# design.net
KiCad netlist of a schematic drawn in Altium Designer
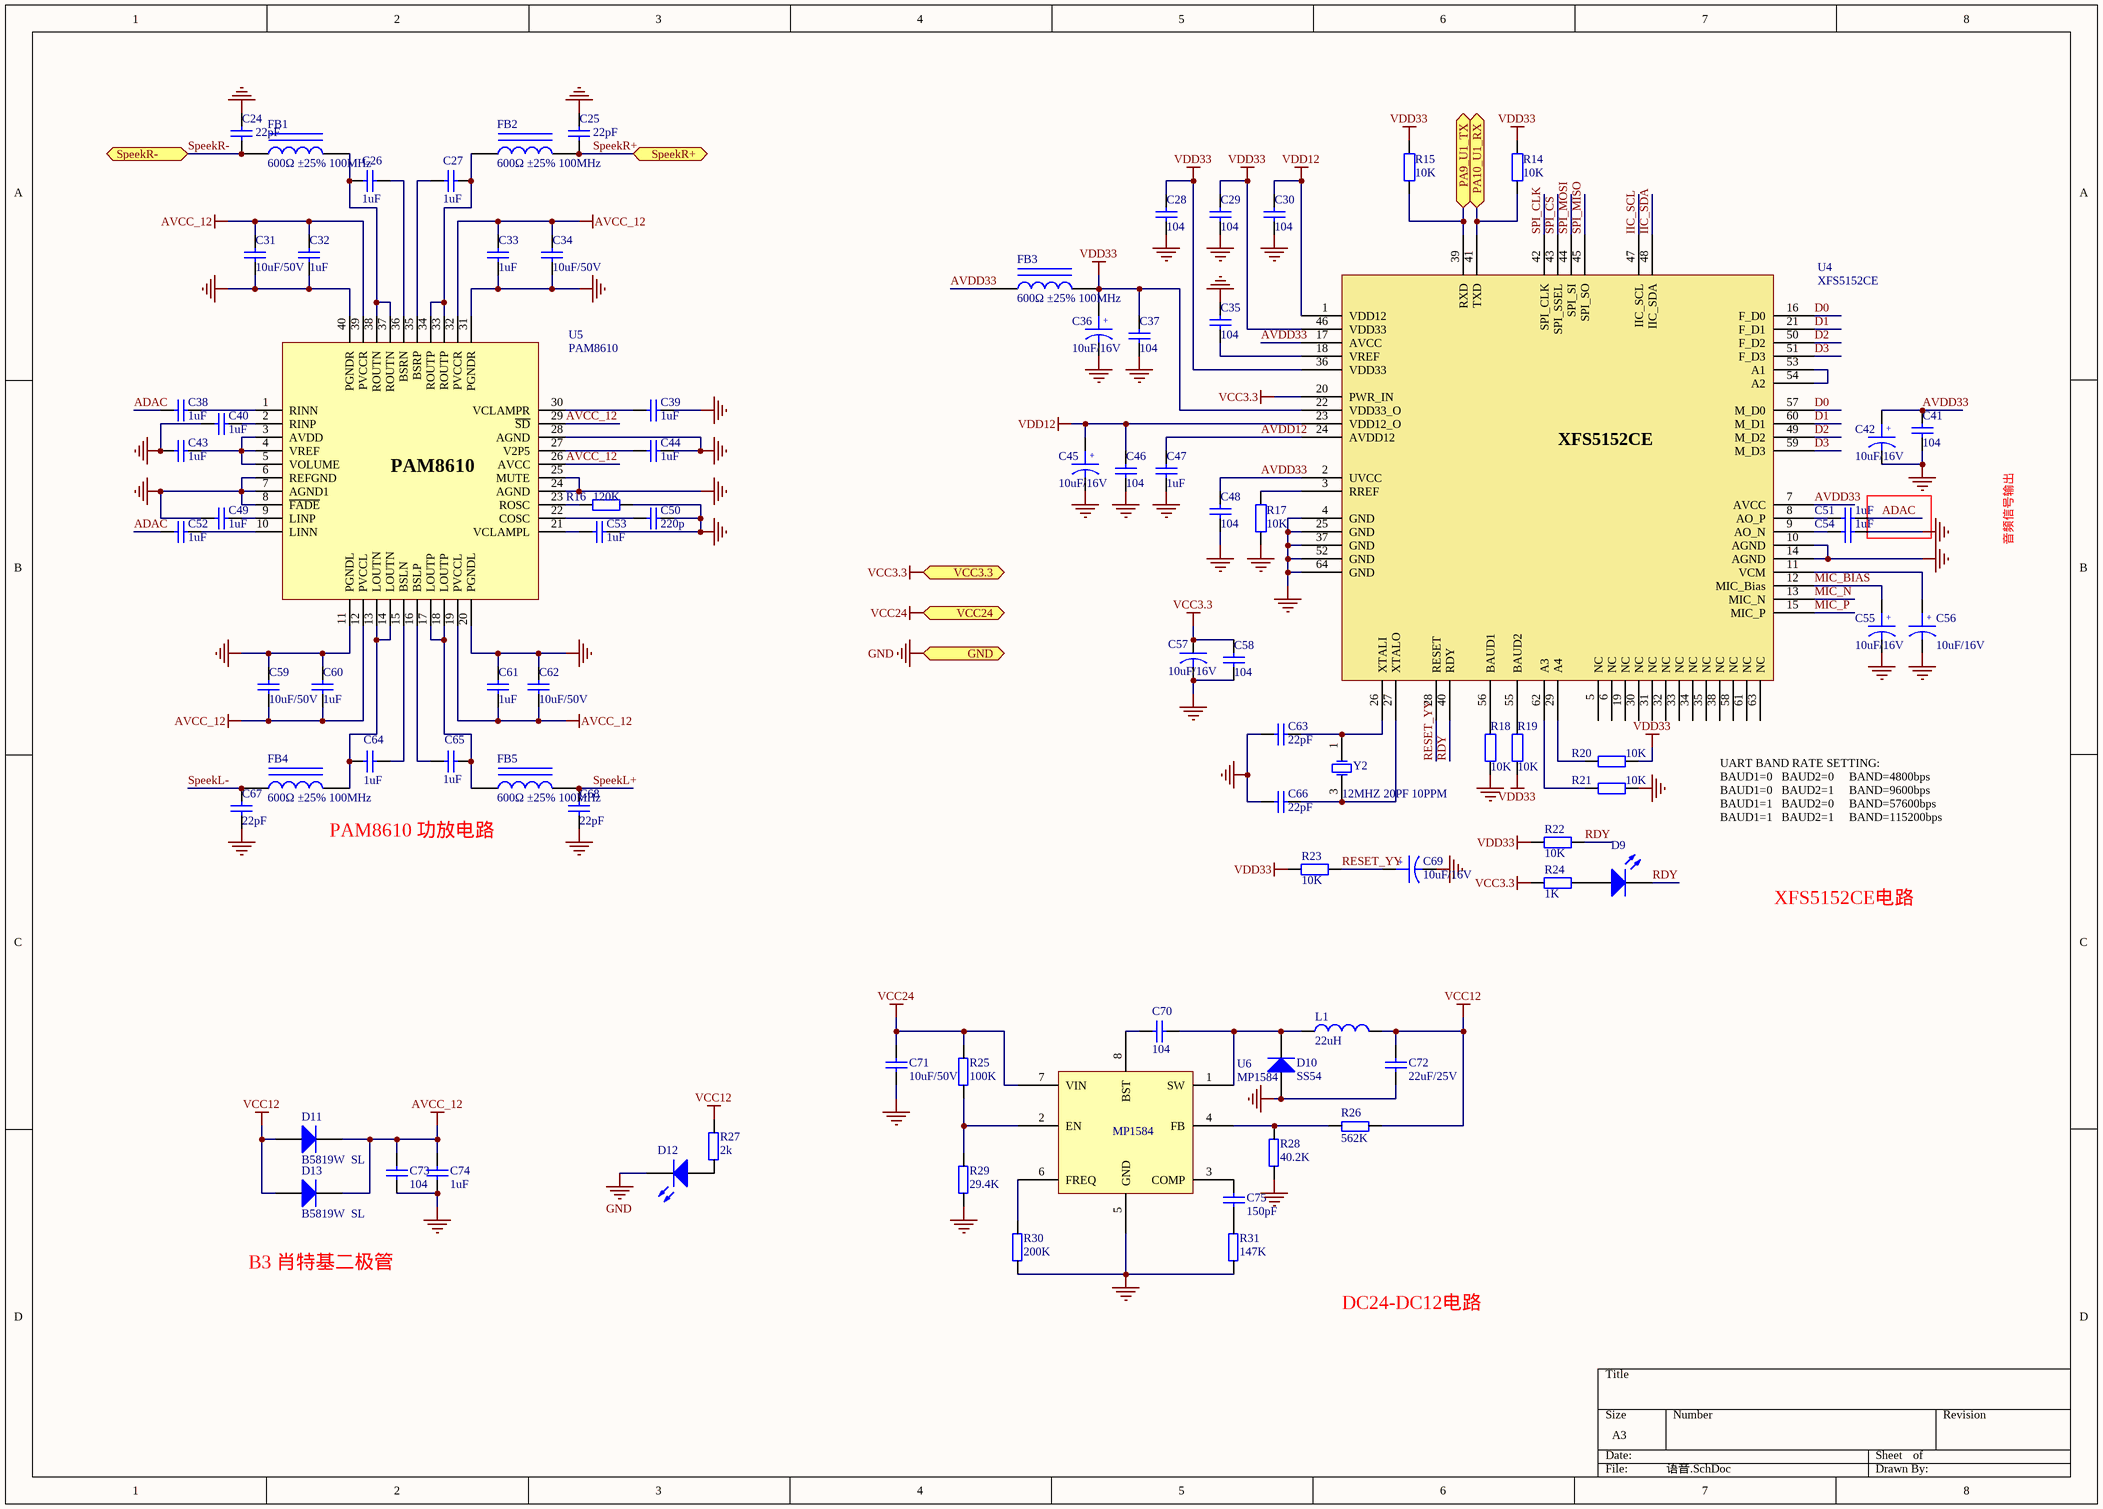
[diagram p0: 语音.SchDoc]

(export (version "E")
  (design (tool "Eeschema 10.0.6"))
  (components
    (comp (ref "C24")
      (value "22pF")
      (footprint "0603_C")
      (description "Capacitor (Semiconductor SIM Model)")
      (fields (field (name "PUBLISHER") "Altium Limited"))
      (libsource (lib "Miscellaneous Devices") (part "Cap Semi"))
    )
    (comp (ref "C25")
      (value "22pF")
      (footprint "0603_C")
      (description "Capacitor (Semiconductor SIM Model)")
      (fields (field (name "PUBLISHER") "Altium Limited"))
      (libsource (lib "Miscellaneous Devices") (part "Cap Semi"))
    )
    (comp (ref "C26")
      (value "1uF")
      (footprint "0603_C")
      (description "Capacitor (Semiconductor SIM Model)")
      (fields (field (name "PUBLISHER") "Altium Limited"))
      (libsource (lib "Miscellaneous Devices") (part "Cap Semi"))
    )
    (comp (ref "C27")
      (value "1uF")
      (footprint "0603_C")
      (description "Capacitor (Semiconductor SIM Model)")
      (fields (field (name "PUBLISHER") "Altium Limited"))
      (libsource (lib "Miscellaneous Devices") (part "Cap Semi"))
    )
    (comp (ref "C28")
      (value "104")
      (footprint "0603_C")
      (description "Capacitor (Semiconductor SIM Model)")
      (fields (field (name "PUBLISHER") "Altium Limited"))
      (libsource (lib "Miscellaneous Devices") (part "Cap Semi"))
    )
    (comp (ref "C29")
      (value "104")
      (footprint "0603_C")
      (description "Capacitor (Semiconductor SIM Model)")
      (fields (field (name "PUBLISHER") "Altium Limited"))
      (libsource (lib "Miscellaneous Devices") (part "Cap Semi"))
    )
    (comp (ref "C30")
      (value "104")
      (footprint "0603_C")
      (description "Capacitor (Semiconductor SIM Model)")
      (fields (field (name "PUBLISHER") "Altium Limited"))
      (libsource (lib "Miscellaneous Devices") (part "Cap Semi"))
    )
    (comp (ref "C31")
      (value "10uF/50V")
      (footprint "1206_C")
      (description "电容")
      (fields (field (name "PUBLISHER") "Altium Limited"))
      (libsource (lib "*") (part "Cap NP"))
    )
    (comp (ref "C32")
      (value "1uF")
      (footprint "0603_C")
      (description "Capacitor (Semiconductor SIM Model)")
      (fields (field (name "PUBLISHER") "Altium Limited"))
      (libsource (lib "Miscellaneous Devices") (part "Cap Semi"))
    )
    (comp (ref "C33")
      (value "1uF")
      (footprint "0603_C")
      (description "Capacitor (Semiconductor SIM Model)")
      (fields (field (name "PUBLISHER") "Altium Limited"))
      (libsource (lib "Miscellaneous Devices") (part "Cap Semi"))
    )
    (comp (ref "C34")
      (value "10uF/50V")
      (footprint "1206_C")
      (description "电容")
      (fields (field (name "PUBLISHER") "Altium Limited"))
      (libsource (lib "*") (part "Cap NP"))
    )
    (comp (ref "C35")
      (value "104")
      (footprint "0603_C")
      (description "Capacitor (Semiconductor SIM Model)")
      (fields (field (name "PUBLISHER") "Altium Limited"))
      (libsource (lib "Miscellaneous Devices") (part "Cap Semi"))
    )
    (comp (ref "C36") (value "10uF/16V") (footprint "3216") (libsource (lib "*") (part "CAP POL")))
    (comp (ref "C37")
      (value "104")
      (footprint "0603_C")
      (description "Capacitor (Semiconductor SIM Model)")
      (fields (field (name "PUBLISHER") "Altium Limited"))
      (libsource (lib "Miscellaneous Devices") (part "Cap Semi"))
    )
    (comp (ref "C38")
      (value "1uF")
      (footprint "0603_C")
      (description "Capacitor (Semiconductor SIM Model)")
      (fields (field (name "PUBLISHER") "Altium Limited"))
      (libsource (lib "Miscellaneous Devices") (part "Cap Semi"))
    )
    (comp (ref "C39")
      (value "1uF")
      (footprint "0603_C")
      (description "Capacitor (Semiconductor SIM Model)")
      (fields (field (name "PUBLISHER") "Altium Limited"))
      (libsource (lib "Miscellaneous Devices") (part "Cap Semi"))
    )
    (comp (ref "C40")
      (value "1uF")
      (footprint "0603_C")
      (description "Capacitor (Semiconductor SIM Model)")
      (fields (field (name "PUBLISHER") "Altium Limited"))
      (libsource (lib "Miscellaneous Devices") (part "Cap Semi"))
    )
    (comp (ref "C41")
      (value "104")
      (footprint "0603_C")
      (description "Capacitor (Semiconductor SIM Model)")
      (fields (field (name "PUBLISHER") "Altium Limited"))
      (libsource (lib "Miscellaneous Devices") (part "Cap Semi"))
    )
    (comp (ref "C42") (value "10uF/16V") (footprint "3216") (libsource (lib "*") (part "CAP POL")))
    (comp (ref "C43")
      (value "1uF")
      (footprint "0603_C")
      (description "Capacitor (Semiconductor SIM Model)")
      (fields (field (name "PUBLISHER") "Altium Limited"))
      (libsource (lib "Miscellaneous Devices") (part "Cap Semi"))
    )
    (comp (ref "C44")
      (value "1uF")
      (footprint "0603_C")
      (description "Capacitor (Semiconductor SIM Model)")
      (fields (field (name "PUBLISHER") "Altium Limited"))
      (libsource (lib "Miscellaneous Devices") (part "Cap Semi"))
    )
    (comp (ref "C45") (value "10uF/16V") (footprint "3216") (libsource (lib "*") (part "CAP POL")))
    (comp (ref "C46")
      (value "104")
      (footprint "0603_C")
      (description "Capacitor (Semiconductor SIM Model)")
      (fields (field (name "PUBLISHER") "Altium Limited"))
      (libsource (lib "Miscellaneous Devices") (part "Cap Semi"))
    )
    (comp (ref "C47")
      (value "1uF")
      (footprint "0603_C")
      (description "Capacitor (Semiconductor SIM Model)")
      (fields (field (name "PUBLISHER") "Altium Limited"))
      (libsource (lib "Miscellaneous Devices") (part "Cap Semi"))
    )
    (comp (ref "C48")
      (value "104")
      (footprint "0603_C")
      (description "Capacitor (Semiconductor SIM Model)")
      (fields (field (name "PUBLISHER") "Altium Limited"))
      (libsource (lib "Miscellaneous Devices") (part "Cap Semi"))
    )
    (comp (ref "C49")
      (value "1uF")
      (footprint "0603_C")
      (description "Capacitor (Semiconductor SIM Model)")
      (fields (field (name "PUBLISHER") "Altium Limited"))
      (libsource (lib "Miscellaneous Devices") (part "Cap Semi"))
    )
    (comp (ref "C50")
      (value "220p")
      (footprint "0603_C")
      (description "Capacitor (Semiconductor SIM Model)")
      (fields (field (name "PUBLISHER") "Altium Limited"))
      (libsource (lib "Miscellaneous Devices") (part "Cap Semi"))
    )
    (comp (ref "C51")
      (value "1uF")
      (footprint "0603_C")
      (description "Capacitor (Semiconductor SIM Model)")
      (fields (field (name "PUBLISHER") "Altium Limited"))
      (libsource (lib "Miscellaneous Devices") (part "Cap Semi"))
    )
    (comp (ref "C52")
      (value "1uF")
      (footprint "0603_C")
      (description "Capacitor (Semiconductor SIM Model)")
      (fields (field (name "PUBLISHER") "Altium Limited"))
      (libsource (lib "Miscellaneous Devices") (part "Cap Semi"))
    )
    (comp (ref "C53")
      (value "1uF")
      (footprint "0603_C")
      (description "Capacitor (Semiconductor SIM Model)")
      (fields (field (name "PUBLISHER") "Altium Limited"))
      (libsource (lib "Miscellaneous Devices") (part "Cap Semi"))
    )
    (comp (ref "C54")
      (value "1uF")
      (footprint "0603_C")
      (description "Capacitor (Semiconductor SIM Model)")
      (fields (field (name "PUBLISHER") "Altium Limited"))
      (libsource (lib "Miscellaneous Devices") (part "Cap Semi"))
    )
    (comp (ref "C55") (value "10uF/16V") (footprint "3216") (libsource (lib "*") (part "CAP POL")))
    (comp (ref "C56") (value "10uF/16V") (footprint "3216") (libsource (lib "*") (part "CAP POL")))
    (comp (ref "C57")
      (value "10uF/16V")
      (footprint "3216")
      (description "Capacitor")
      (libsource (lib "*") (part "CAPACITOR"))
    )
    (comp (ref "C58")
      (value "104")
      (footprint "0603_C")
      (description "Capacitor (Semiconductor SIM Model)")
      (fields (field (name "PUBLISHER") "Altium Limited"))
      (libsource (lib "Miscellaneous Devices") (part "Cap Semi"))
    )
    (comp (ref "C59")
      (value "10uF/50V")
      (footprint "1206_C")
      (description "电容")
      (fields (field (name "PUBLISHER") "Altium Limited"))
      (libsource (lib "*") (part "Cap NP"))
    )
    (comp (ref "C60")
      (value "1uF")
      (footprint "0603_C")
      (description "Capacitor (Semiconductor SIM Model)")
      (fields (field (name "PUBLISHER") "Altium Limited"))
      (libsource (lib "Miscellaneous Devices") (part "Cap Semi"))
    )
    (comp (ref "C61")
      (value "1uF")
      (footprint "0603_C")
      (description "Capacitor (Semiconductor SIM Model)")
      (fields (field (name "PUBLISHER") "Altium Limited"))
      (libsource (lib "Miscellaneous Devices") (part "Cap Semi"))
    )
    (comp (ref "C62")
      (value "10uF/50V")
      (footprint "1206_C")
      (description "电容")
      (fields (field (name "PUBLISHER") "Altium Limited"))
      (libsource (lib "*") (part "Cap NP"))
    )
    (comp (ref "C63")
      (value "22pF")
      (footprint "0603_C")
      (description "电容")
      (fields (field (name "PUBLISHER") "Altium Limited"))
      (libsource (lib "*") (part "Cap NP"))
    )
    (comp (ref "C64")
      (value "1uF")
      (footprint "0603_C")
      (description "Capacitor (Semiconductor SIM Model)")
      (fields (field (name "PUBLISHER") "Altium Limited"))
      (libsource (lib "Miscellaneous Devices") (part "Cap Semi"))
    )
    (comp (ref "C65")
      (value "1uF")
      (footprint "0603_C")
      (description "Capacitor (Semiconductor SIM Model)")
      (fields (field (name "PUBLISHER") "Altium Limited"))
      (libsource (lib "Miscellaneous Devices") (part "Cap Semi"))
    )
    (comp (ref "C66")
      (value "22pF")
      (footprint "0603_C")
      (description "电容")
      (fields (field (name "PUBLISHER") "Altium Limited"))
      (libsource (lib "*") (part "Cap NP"))
    )
    (comp (ref "C67")
      (value "22pF")
      (footprint "0603_C")
      (description "Capacitor (Semiconductor SIM Model)")
      (fields (field (name "PUBLISHER") "Altium Limited"))
      (libsource (lib "Miscellaneous Devices") (part "Cap Semi"))
    )
    (comp (ref "C68")
      (value "22pF")
      (footprint "0603_C")
      (description "Capacitor (Semiconductor SIM Model)")
      (fields (field (name "PUBLISHER") "Altium Limited"))
      (libsource (lib "Miscellaneous Devices") (part "Cap Semi"))
    )
    (comp (ref "C69") (value "10uF/16V") (footprint "3216") (libsource (lib "*") (part "CAP POL")))
    (comp (ref "C70")
      (value "104")
      (footprint "0603_C")
      (description "Capacitor (Semiconductor SIM Model)")
      (fields (field (name "PUBLISHER") "Altium Limited"))
      (libsource (lib "Miscellaneous Devices") (part "Cap Semi"))
    )
    (comp (ref "C71")
      (value "10uF/50V")
      (footprint "1206_C")
      (description "Capacitor (Semiconductor SIM Model)")
      (fields (field (name "PUBLISHER") "Altium Limited"))
      (libsource (lib "Miscellaneous Devices") (part "Cap Semi"))
    )
    (comp (ref "C72")
      (value "22uF/25V")
      (footprint "0805_C")
      (description "Capacitor (Semiconductor SIM Model)")
      (fields (field (name "PUBLISHER") "Altium Limited"))
      (libsource (lib "Miscellaneous Devices") (part "Cap Semi"))
    )
    (comp (ref "C73")
      (value "104")
      (footprint "0603_C")
      (description "Capacitor (Semiconductor SIM Model)")
      (fields (field (name "PUBLISHER") "Altium Limited"))
      (libsource (lib "Miscellaneous Devices") (part "Cap Semi"))
    )
    (comp (ref "C74")
      (value "1uF")
      (footprint "0603_C")
      (description "Capacitor (Semiconductor SIM Model)")
      (fields (field (name "PUBLISHER") "Altium Limited"))
      (libsource (lib "Miscellaneous Devices") (part "Cap Semi"))
    )
    (comp (ref "C75")
      (value "150pF")
      (footprint "0603_C")
      (description "Capacitor (Semiconductor SIM Model)")
      (fields (field (name "PUBLISHER") "Altium Limited"))
      (libsource (lib "Miscellaneous Devices") (part "Cap Semi"))
    )
    (comp (ref "D9")
      (value "红灯 0805")
      (footprint "LC-0805_LED_S1")
      (description "Typical INFRARED GaAs LED")
      (fields (field (name "PUBLISHER") "Altium Limited"))
      (libsource (lib "继电器板_1") (part "LED0"))
    )
    (comp (ref "D10")
      (value "SS54")
      (footprint "SMA(DO-214AC)_S1")
      (description "二极管")
      (libsource (lib "Miscellaneous Devices LC") (part "SMA(DO-214AC) SS54"))
    )
    (comp (ref "D11")
      (value "B5819W  SL")
      (footprint "SOD-123")
      (description "肖特基二极管")
      (libsource (lib "Miscellaneous Devices LC") (part "SOD-123 B5819W  SL"))
    )
    (comp (ref "D12")
      (value "蓝灯 0805")
      (footprint "LC-0805_LED_S1")
      (description "Typical INFRARED GaAs LED")
      (fields (field (name "PUBLISHER") "Altium Limited"))
      (libsource (lib "继电器板_1") (part "LED0"))
    )
    (comp (ref "D13")
      (value "B5819W  SL")
      (footprint "SOD-123")
      (description "肖特基二极管")
      (libsource (lib "Miscellaneous Devices LC") (part "SOD-123 B5819W  SL"))
    )
    (comp (ref "FB1")
      (value "600Ω ±25% 100MHz")
      (footprint "0805_L")
      (description "贴片磁珠")
      (libsource (lib "Miscellaneous Devices LC") (part "0805 600Ω 25% 100MHz"))
    )
    (comp (ref "FB2")
      (value "600Ω ±25% 100MHz")
      (footprint "0805_L")
      (description "贴片磁珠")
      (libsource (lib "Miscellaneous Devices LC") (part "0805 600Ω 25% 100MHz"))
    )
    (comp (ref "FB3")
      (value "600Ω ±25% 100MHz")
      (footprint "0805_L")
      (description "贴片磁珠")
      (libsource (lib "Miscellaneous Devices LC") (part "0805 600Ω 25% 100MHz"))
    )
    (comp (ref "FB4")
      (value "600Ω ±25% 100MHz")
      (footprint "0805_L")
      (description "贴片磁珠")
      (libsource (lib "Miscellaneous Devices LC") (part "0805 600Ω 25% 100MHz"))
    )
    (comp (ref "FB5")
      (value "600Ω ±25% 100MHz")
      (footprint "0805_L")
      (description "贴片磁珠")
      (libsource (lib "Miscellaneous Devices LC") (part "0805 600Ω 25% 100MHz"))
    )
    (comp (ref "L1")
      (value "22uH")
      (footprint "L-7*7*4mm-S")
      (description "Inductor")
      (fields (field (name "PUBLISHER") "Altium Limited"))
      (libsource (lib "Miscellaneous Devices") (part "Inductor"))
    )
    (comp (ref "R14")
      (value "10K")
      (footprint "0603_R")
      (description "Resistor")
      (fields (field (name "PUBLISHER") "Altium Limited"))
      (libsource (lib "") (part "Res2_3"))
    )
    (comp (ref "R15")
      (value "10K")
      (footprint "0603_R")
      (description "Resistor")
      (fields (field (name "PUBLISHER") "Altium Limited"))
      (libsource (lib "") (part "Res2_1"))
    )
    (comp (ref "R16")
      (value "120K")
      (footprint "0603_R")
      (description "Resistor")
      (fields (field (name "PUBLISHER") "Altium Limited"))
      (libsource (lib "") (part "Res2_2"))
    )
    (comp (ref "R17")
      (value "10K")
      (footprint "0603_R")
      (description "Resistor")
      (fields (field (name "PUBLISHER") "Altium Limited"))
      (libsource (lib "") (part "Res2_3"))
    )
    (comp (ref "R18")
      (value "10K")
      (footprint "0603_R")
      (description "Resistor")
      (fields (field (name "PUBLISHER") "Altium Limited"))
      (libsource (lib "") (part "Res2_1"))
    )
    (comp (ref "R19")
      (value "10K")
      (footprint "0603_R")
      (description "Resistor")
      (fields (field (name "PUBLISHER") "Altium Limited"))
      (libsource (lib "") (part "Res2_1"))
    )
    (comp (ref "R20")
      (value "10K")
      (footprint "0603_R")
      (description "Resistor")
      (fields (field (name "PUBLISHER") "Altium Limited"))
      (libsource (lib "*") (part "Res2"))
    )
    (comp (ref "R21")
      (value "10K")
      (footprint "0603_R")
      (description "Resistor")
      (fields (field (name "PUBLISHER") "Altium Limited"))
      (libsource (lib "") (part "Res2_2"))
    )
    (comp (ref "R22")
      (value "10K")
      (footprint "0603_R")
      (description "Resistor")
      (fields (field (name "PUBLISHER") "Altium Limited"))
      (libsource (lib "*") (part "Res2"))
    )
    (comp (ref "R23")
      (value "10K")
      (footprint "0603_R")
      (description "Resistor")
      (fields (field (name "PUBLISHER") "Altium Limited"))
      (libsource (lib "*") (part "Res2"))
    )
    (comp (ref "R24")
      (value "1K")
      (footprint "0603_R")
      (description "Resistor")
      (fields (field (name "PUBLISHER") "Altium Limited"))
      (libsource (lib "*") (part "Res2"))
    )
    (comp (ref "R25")
      (value "100K")
      (footprint "0603_R")
      (libsource (lib "Explorer STM32F407封装库") (part "R_2"))
    )
    (comp (ref "R26")
      (value "562K")
      (footprint "0603_R")
      (libsource (lib "Explorer STM32F407封装库") (part "R_2"))
    )
    (comp (ref "R27")
      (value "2k")
      (footprint "0603_R")
      (libsource (lib "Explorer STM32F407封装库") (part "R_2"))
    )
    (comp (ref "R28")
      (value "40.2K")
      (footprint "0603_R")
      (libsource (lib "Explorer STM32F407封装库") (part "R_2"))
    )
    (comp (ref "R29")
      (value "29.4K")
      (footprint "0603_R")
      (libsource (lib "Explorer STM32F407封装库") (part "R_2"))
    )
    (comp (ref "R30")
      (value "200K")
      (footprint "0603_R")
      (libsource (lib "Explorer STM32F407封装库") (part "R_2"))
    )
    (comp (ref "R31")
      (value "147K")
      (footprint "0603_R")
      (libsource (lib "Explorer STM32F407封装库") (part "R_2"))
    )
    (comp (ref "U4")
      (value "XFS5152CE")
      (footprint "LQFP-64_10x10x05P")
      (libsource (lib "*") (part "XFS5152-2"))
    )
    (comp (ref "U5")
      (value "PAM8610")
      (footprint "QFN50P600X600X80-40N")
      (libsource (lib "my third") (part "PAM8610功放芯片"))
    )
    (comp (ref "U6")
      (value "MP1584")
      (footprint "LC-SOIC-8_EP_150MIL")
      (libsource (lib "磁导航") (part "MP1584EN"))
    )
    (comp (ref "Y2")
      (value "12MHZ 20PF 10PPM")
      (footprint "SMD-3225_4P")
      (description "贴片晶振")
      (libsource (lib "Miscellaneous Devices LC") (part "SMD-3225_4P  12MHZ 20PF 10PPM"))
    )
  )
  (nets
    (net (code "1") (name "/ADAC") (class "Default")
      (node (ref "C38") (pin "1") (pinfunction "1_1") (pintype "passive"))
      (node (ref "C51") (pin "1") (pinfunction "1_1") (pintype "passive"))
      (node (ref "C52") (pin "1") (pinfunction "1_1") (pintype "passive"))
    )
    (net (code "2") (name "/AVDD12") (class "Default")
      (node (ref "C47") (pin "2") (pinfunction "2_2") (pintype "passive"))
      (node (ref "U4") (pin "24") (pinfunction "AVDD12_24") (pintype "passive"))
    )
    (net (code "3") (name "/AVDD33") (class "Default")
      (node (ref "C41") (pin "1") (pinfunction "1_1") (pintype "passive"))
      (node (ref "C42") (pin "1") (pinfunction "1_1") (pintype "passive"))
      (node (ref "C48") (pin "1") (pinfunction "1_1") (pintype "passive"))
      (node (ref "FB3") (pin "1") (pinfunction "1_1") (pintype "passive"))
      (node (ref "U4") (pin "17") (pinfunction "AVCC_17") (pintype "passive"))
      (node (ref "U4") (pin "2") (pinfunction "UVCC_2") (pintype "passive"))
      (node (ref "U4") (pin "7") (pinfunction "AVCC_7") (pintype "passive"))
    )
    (net (code "4") (name "/D0") (class "Default")
      (node (ref "U4") (pin "16") (pinfunction "F_D0_16") (pintype "passive"))
      (node (ref "U4") (pin "57") (pinfunction "M_D0_57") (pintype "passive"))
    )
    (net (code "5") (name "/D1") (class "Default")
      (node (ref "U4") (pin "21") (pinfunction "F_D1_21") (pintype "passive"))
      (node (ref "U4") (pin "60") (pinfunction "M_D1_60") (pintype "passive"))
    )
    (net (code "6") (name "/D2") (class "Default")
      (node (ref "U4") (pin "49") (pinfunction "M_D2_49") (pintype "passive"))
      (node (ref "U4") (pin "50") (pinfunction "F_D2_50") (pintype "passive"))
    )
    (net (code "7") (name "/D3") (class "Default")
      (node (ref "U4") (pin "51") (pinfunction "F_D3_51") (pintype "passive"))
      (node (ref "U4") (pin "59") (pinfunction "M_D3_59") (pintype "passive"))
    )
    (net (code "8") (name "/IIC_SCL") (class "Default")
      (node (ref "U4") (pin "47") (pinfunction "IIC_SCL_47") (pintype "passive"))
    )
    (net (code "9") (name "/IIC_SDA") (class "Default")
      (node (ref "U4") (pin "48") (pinfunction "IIC_SDA_48") (pintype "passive"))
    )
    (net (code "10") (name "/MIC_BIAS") (class "Default")
      (node (ref "C55") (pin "1") (pinfunction "1_1") (pintype "passive"))
      (node (ref "U4") (pin "12") (pinfunction "MIC_Bias_12") (pintype "passive"))
    )
    (net (code "11") (name "/MIC_N") (class "Default")
      (node (ref "U4") (pin "13") (pinfunction "MIC_N_13") (pintype "passive"))
    )
    (net (code "12") (name "/MIC_P") (class "Default")
      (node (ref "U4") (pin "15") (pinfunction "MIC_P_15") (pintype "passive"))
    )
    (net (code "13") (name "/PA9_U1_TX") (class "Default")
      (node (ref "R15") (pin "2") (pinfunction "2_2") (pintype "passive"))
      (node (ref "U4") (pin "39") (pinfunction "RXD_39") (pintype "passive"))
    )
    (net (code "14") (name "/PA10_U1_RX") (class "Default")
      (node (ref "R14") (pin "1") (pinfunction "1_1") (pintype "passive"))
      (node (ref "U4") (pin "41") (pinfunction "TXD_41") (pintype "passive"))
    )
    (net (code "15") (name "/RDY") (class "Default")
      (node (ref "D9") (pin "K") (pinfunction "K_K") (pintype "passive"))
      (node (ref "R22") (pin "2") (pinfunction "2_2") (pintype "passive"))
      (node (ref "U4") (pin "40") (pinfunction "RDY_40") (pintype "passive"))
    )
    (net (code "16") (name "/RESET_YY") (class "Default")
      (node (ref "C69") (pin "1") (pinfunction "1_1") (pintype "passive"))
      (node (ref "R23") (pin "2") (pinfunction "2_2") (pintype "passive"))
      (node (ref "U4") (pin "28") (pinfunction "RESET_28") (pintype "passive"))
    )
    (net (code "17") (name "/SPI_CLK") (class "Default")
      (node (ref "U4") (pin "42") (pinfunction "SPI_CLK_42") (pintype "passive"))
    )
    (net (code "18") (name "/SPI_CS") (class "Default")
      (node (ref "U4") (pin "43") (pinfunction "SPI_SSEL_43") (pintype "passive"))
    )
    (net (code "19") (name "/SPI_MISO") (class "Default")
      (node (ref "U4") (pin "45") (pinfunction "SPI_SO_45") (pintype "passive"))
    )
    (net (code "20") (name "/SPI_MOSI") (class "Default")
      (node (ref "U4") (pin "44") (pinfunction "SPI_SI_44") (pintype "passive"))
    )
    (net (code "21") (name "/SpeekL+") (class "Default")
      (node (ref "C68") (pin "2") (pinfunction "2_2") (pintype "passive"))
      (node (ref "FB5") (pin "2") (pinfunction "2_2") (pintype "passive"))
    )
    (net (code "22") (name "/SpeekL-") (class "Default")
      (node (ref "C67") (pin "2") (pinfunction "2_2") (pintype "passive"))
      (node (ref "FB4") (pin "1") (pinfunction "1_1") (pintype "passive"))
    )
    (net (code "23") (name "/SpeekR+") (class "Default")
      (node (ref "C25") (pin "2") (pinfunction "2_2") (pintype "passive"))
      (node (ref "FB2") (pin "2") (pinfunction "2_2") (pintype "passive"))
    )
    (net (code "24") (name "/SpeekR-") (class "Default")
      (node (ref "C24") (pin "2") (pinfunction "2_2") (pintype "passive"))
      (node (ref "FB1") (pin "1") (pinfunction "1_1") (pintype "passive"))
    )
    (net (code "25") (name "AVCC_12") (class "Default")
      (node (ref "C31") (pin "1") (pinfunction "1_1") (pintype "passive"))
      (node (ref "C32") (pin "1") (pinfunction "1_1") (pintype "passive"))
      (node (ref "C33") (pin "1") (pinfunction "1_1") (pintype "passive"))
      (node (ref "C34") (pin "1") (pinfunction "1_1") (pintype "passive"))
      (node (ref "C59") (pin "1") (pinfunction "1_1") (pintype "passive"))
      (node (ref "C60") (pin "1") (pinfunction "1_1") (pintype "passive"))
      (node (ref "C61") (pin "1") (pinfunction "1_1") (pintype "passive"))
      (node (ref "C62") (pin "1") (pinfunction "1_1") (pintype "passive"))
      (node (ref "C73") (pin "1") (pinfunction "1_1") (pintype "passive"))
      (node (ref "C74") (pin "1") (pinfunction "1_1") (pintype "passive"))
      (node (ref "D11") (pin "2") (pinfunction "K_2") (pintype "passive"))
      (node (ref "D13") (pin "2") (pinfunction "K_2") (pintype "passive"))
      (node (ref "U5") (pin "12") (pinfunction "PVCCL_12") (pintype "passive"))
      (node (ref "U5") (pin "19") (pinfunction "PVCCL_19") (pintype "passive"))
      (node (ref "U5") (pin "26") (pinfunction "AVCC_26") (pintype "passive"))
      (node (ref "U5") (pin "29") (pinfunction "~{SD}_29") (pintype "passive"))
      (node (ref "U5") (pin "32") (pinfunction "PVCCR_32") (pintype "passive"))
      (node (ref "U5") (pin "39") (pinfunction "PVCCR_39") (pintype "passive"))
    )
    (net (code "26") (name "GND") (class "Default")
      (node (ref "C24") (pin "1") (pinfunction "1_1") (pintype "passive"))
      (node (ref "C25") (pin "1") (pinfunction "1_1") (pintype "passive"))
      (node (ref "C28") (pin "2") (pinfunction "2_2") (pintype "passive"))
      (node (ref "C29") (pin "2") (pinfunction "2_2") (pintype "passive"))
      (node (ref "C30") (pin "2") (pinfunction "2_2") (pintype "passive"))
      (node (ref "C31") (pin "2") (pinfunction "2_2") (pintype "passive"))
      (node (ref "C32") (pin "2") (pinfunction "2_2") (pintype "passive"))
      (node (ref "C33") (pin "2") (pinfunction "2_2") (pintype "passive"))
      (node (ref "C34") (pin "2") (pinfunction "2_2") (pintype "passive"))
      (node (ref "C35") (pin "1") (pinfunction "1_1") (pintype "passive"))
      (node (ref "C36") (pin "2") (pinfunction "2_2") (pintype "passive"))
      (node (ref "C37") (pin "2") (pinfunction "2_2") (pintype "passive"))
      (node (ref "C39") (pin "2") (pinfunction "2_2") (pintype "passive"))
      (node (ref "C40") (pin "1") (pinfunction "1_1") (pintype "passive"))
      (node (ref "C41") (pin "2") (pinfunction "2_2") (pintype "passive"))
      (node (ref "C42") (pin "2") (pinfunction "2_2") (pintype "passive"))
      (node (ref "C43") (pin "1") (pinfunction "1_1") (pintype "passive"))
      (node (ref "C44") (pin "2") (pinfunction "2_2") (pintype "passive"))
      (node (ref "C45") (pin "2") (pinfunction "2_2") (pintype "passive"))
      (node (ref "C46") (pin "2") (pinfunction "2_2") (pintype "passive"))
      (node (ref "C47") (pin "1") (pinfunction "1_1") (pintype "passive"))
      (node (ref "C48") (pin "2") (pinfunction "2_2") (pintype "passive"))
      (node (ref "C49") (pin "1") (pinfunction "1_1") (pintype "passive"))
      (node (ref "C50") (pin "2") (pinfunction "2_2") (pintype "passive"))
      (node (ref "C53") (pin "2") (pinfunction "2_2") (pintype "passive"))
      (node (ref "C54") (pin "1") (pinfunction "1_1") (pintype "passive"))
      (node (ref "C55") (pin "2") (pinfunction "2_2") (pintype "passive"))
      (node (ref "C56") (pin "2") (pinfunction "2_2") (pintype "passive"))
      (node (ref "C57") (pin "2") (pinfunction "2_2") (pintype "passive"))
      (node (ref "C58") (pin "2") (pinfunction "2_2") (pintype "passive"))
      (node (ref "C59") (pin "2") (pinfunction "2_2") (pintype "passive"))
      (node (ref "C60") (pin "2") (pinfunction "2_2") (pintype "passive"))
      (node (ref "C61") (pin "2") (pinfunction "2_2") (pintype "passive"))
      (node (ref "C62") (pin "2") (pinfunction "2_2") (pintype "passive"))
      (node (ref "C63") (pin "1") (pinfunction "1_1") (pintype "passive"))
      (node (ref "C66") (pin "1") (pinfunction "1_1") (pintype "passive"))
      (node (ref "C67") (pin "1") (pinfunction "1_1") (pintype "passive"))
      (node (ref "C68") (pin "1") (pinfunction "1_1") (pintype "passive"))
      (node (ref "C69") (pin "2") (pinfunction "2_2") (pintype "passive"))
      (node (ref "C71") (pin "2") (pinfunction "2_2") (pintype "passive"))
      (node (ref "C72") (pin "1") (pinfunction "1_1") (pintype "passive"))
      (node (ref "C73") (pin "2") (pinfunction "2_2") (pintype "passive"))
      (node (ref "C74") (pin "2") (pinfunction "2_2") (pintype "passive"))
      (node (ref "D10") (pin "1") (pinfunction "A_1") (pintype "passive"))
      (node (ref "D12") (pin "K") (pinfunction "K_K") (pintype "passive"))
      (node (ref "R16") (pin "1") (pinfunction "1_1") (pintype "passive"))
      (node (ref "R17") (pin "1") (pinfunction "1_1") (pintype "passive"))
      (node (ref "R18") (pin "2") (pinfunction "2_2") (pintype "passive"))
      (node (ref "R21") (pin "1") (pinfunction "1_1") (pintype "passive"))
      (node (ref "R28") (pin "2") (pintype "passive"))
      (node (ref "R29") (pin "2") (pintype "passive"))
      (node (ref "R30") (pin "2") (pintype "passive"))
      (node (ref "R31") (pin "2") (pintype "passive"))
      (node (ref "U4") (pin "10") (pinfunction "AGND_10") (pintype "passive"))
      (node (ref "U4") (pin "14") (pinfunction "AGND_14") (pintype "passive"))
      (node (ref "U4") (pin "25") (pinfunction "GND_25") (pintype "passive"))
      (node (ref "U4") (pin "37") (pinfunction "GND_37") (pintype "passive"))
      (node (ref "U4") (pin "4") (pinfunction "GND_4") (pintype "passive"))
      (node (ref "U4") (pin "52") (pinfunction "GND_52") (pintype "passive"))
      (node (ref "U4") (pin "64") (pinfunction "GND_64") (pintype "passive"))
      (node (ref "U5") (pin "11") (pinfunction "PGNDL_11") (pintype "passive"))
      (node (ref "U5") (pin "20") (pinfunction "PGNDL_20") (pintype "passive"))
      (node (ref "U5") (pin "24") (pinfunction "AGND_24") (pintype "passive"))
      (node (ref "U5") (pin "25") (pinfunction "MUTE_25") (pintype "passive"))
      (node (ref "U5") (pin "28") (pinfunction "AGND_28") (pintype "passive"))
      (node (ref "U5") (pin "31") (pinfunction "PGNDR_31") (pintype "passive"))
      (node (ref "U5") (pin "40") (pinfunction "PGNDR_40") (pintype "passive"))
      (node (ref "U5") (pin "6") (pinfunction "REFGND_6") (pintype "passive"))
      (node (ref "U5") (pin "7") (pinfunction "AGND1_7") (pintype "passive"))
      (node (ref "U5") (pin "8") (pinfunction "~{FADE}_8") (pintype "passive"))
      (node (ref "U6") (pin "5") (pinfunction "GND_5") (pintype "passive"))
    )
    (net (code "27") (name "Net-(C26-Pad1)") (class "Default")
      (node (ref "C26") (pin "1") (pinfunction "1_1") (pintype "passive"))
      (node (ref "FB1") (pin "2") (pinfunction "2_2") (pintype "passive"))
      (node (ref "U5") (pin "37") (pinfunction "ROUTN_37") (pintype "passive"))
      (node (ref "U5") (pin "38") (pinfunction "ROUTN_38") (pintype "passive"))
    )
    (net (code "28") (name "Net-(C27-Pad2)") (class "Default")
      (node (ref "C27") (pin "2") (pinfunction "2_2") (pintype "passive"))
      (node (ref "FB2") (pin "1") (pinfunction "1_1") (pintype "passive"))
      (node (ref "U5") (pin "33") (pinfunction "ROUTP_33") (pintype "passive"))
      (node (ref "U5") (pin "34") (pinfunction "ROUTP_34") (pintype "passive"))
    )
    (net (code "29") (name "Net-(C64-Pad2)") (class "Default")
      (node (ref "C64") (pin "2") (pinfunction "2_2") (pintype "passive"))
      (node (ref "FB4") (pin "2") (pinfunction "2_2") (pintype "passive"))
      (node (ref "U5") (pin "13") (pinfunction "LOUTN_13") (pintype "passive"))
      (node (ref "U5") (pin "14") (pinfunction "LOUTN_14") (pintype "passive"))
    )
    (net (code "30") (name "Net-(C65-Pad2)") (class "Default")
      (node (ref "C65") (pin "2") (pinfunction "2_2") (pintype "passive"))
      (node (ref "FB5") (pin "1") (pinfunction "1_1") (pintype "passive"))
      (node (ref "U5") (pin "17") (pinfunction "LOUTP_17") (pintype "passive"))
      (node (ref "U5") (pin "18") (pinfunction "LOUTP_18") (pintype "passive"))
    )
    (net (code "31") (name "Net-(C75-Pad1)") (class "Default")
      (node (ref "C75") (pin "1") (pinfunction "1_1") (pintype "passive"))
      (node (ref "R31") (pin "1") (pintype "passive"))
    )
    (net (code "32") (name "Net-(D9-PadA)") (class "Default")
      (node (ref "D9") (pin "A") (pinfunction "A_A") (pintype "passive"))
      (node (ref "R24") (pin "2") (pinfunction "2_2") (pintype "passive"))
    )
    (net (code "33") (name "Net-(D10-K)") (class "Default")
      (node (ref "C70") (pin "1") (pinfunction "1_1") (pintype "passive"))
      (node (ref "D10") (pin "2") (pinfunction "K_2") (pintype "passive"))
      (node (ref "L1") (pin "1") (pinfunction "1_1") (pintype "passive"))
      (node (ref "U6") (pin "1") (pinfunction "SW_1") (pintype "passive"))
    )
    (net (code "34") (name "Net-(D12-PadA)") (class "Default")
      (node (ref "D12") (pin "A") (pinfunction "A_A") (pintype "passive"))
      (node (ref "R27") (pin "2") (pintype "passive"))
    )
    (net (code "35") (name "Net-(U4-A1)") (class "Default")
      (node (ref "U4") (pin "53") (pinfunction "A1_53") (pintype "passive"))
      (node (ref "U4") (pin "54") (pinfunction "A2_54") (pintype "passive"))
    )
    (net (code "36") (name "Net-(U4-A3)") (class "Default")
      (node (ref "R21") (pin "2") (pinfunction "2_2") (pintype "passive"))
      (node (ref "U4") (pin "62") (pinfunction "A3_62") (pintype "passive"))
    )
    (net (code "37") (name "Net-(U4-A4)") (class "Default")
      (node (ref "R20") (pin "1") (pinfunction "1_1") (pintype "passive"))
      (node (ref "U4") (pin "29") (pinfunction "A4_29") (pintype "passive"))
    )
    (net (code "38") (name "Net-(U4-AO_N)") (class "Default")
      (node (ref "C54") (pin "2") (pinfunction "2_2") (pintype "passive"))
      (node (ref "U4") (pin "9") (pinfunction "AO_N_9") (pintype "passive"))
    )
    (net (code "39") (name "Net-(U4-AO_P)") (class "Default")
      (node (ref "C51") (pin "2") (pinfunction "2_2") (pintype "passive"))
      (node (ref "U4") (pin "8") (pinfunction "AO_P_8") (pintype "passive"))
    )
    (net (code "40") (name "Net-(U4-BAUD1)") (class "Default")
      (node (ref "R18") (pin "1") (pinfunction "1_1") (pintype "passive"))
      (node (ref "U4") (pin "56") (pinfunction "BAUD1_56") (pintype "passive"))
    )
    (net (code "41") (name "Net-(U4-BAUD2)") (class "Default")
      (node (ref "R19") (pin "1") (pinfunction "1_1") (pintype "passive"))
      (node (ref "U4") (pin "55") (pinfunction "BAUD2_55") (pintype "passive"))
    )
    (net (code "42") (name "Net-(U4-RREF)") (class "Default")
      (node (ref "R17") (pin "2") (pinfunction "2_2") (pintype "passive"))
      (node (ref "U4") (pin "3") (pinfunction "RREF_3") (pintype "passive"))
    )
    (net (code "43") (name "Net-(U4-VCM)") (class "Default")
      (node (ref "C56") (pin "1") (pinfunction "1_1") (pintype "passive"))
      (node (ref "U4") (pin "11") (pinfunction "VCM_11") (pintype "passive"))
    )
    (net (code "44") (name "Net-(U4-VREF)") (class "Default")
      (node (ref "C35") (pin "2") (pinfunction "2_2") (pintype "passive"))
      (node (ref "U4") (pin "18") (pinfunction "VREF_18") (pintype "passive"))
    )
    (net (code "45") (name "Net-(U4-XTALI)") (class "Default")
      (node (ref "C63") (pin "2") (pinfunction "2_2") (pintype "passive"))
      (node (ref "U4") (pin "26") (pinfunction "XTALI_26") (pintype "passive"))
      (node (ref "Y2") (pin "1") (pinfunction "OSC1_1") (pintype "passive"))
    )
    (net (code "46") (name "Net-(U4-XTALO)") (class "Default")
      (node (ref "C66") (pin "2") (pinfunction "2_2") (pintype "passive"))
      (node (ref "U4") (pin "27") (pinfunction "XTALO_27") (pintype "passive"))
      (node (ref "Y2") (pin "3") (pinfunction "OSC2_3") (pintype "passive"))
    )
    (net (code "47") (name "Net-(U5-AVDD)") (class "Default")
      (node (ref "C43") (pin "2") (pinfunction "2_2") (pintype "passive"))
      (node (ref "U5") (pin "3") (pinfunction "AVDD_3") (pintype "passive"))
      (node (ref "U5") (pin "4") (pinfunction "VREF_4") (pintype "passive"))
      (node (ref "U5") (pin "5") (pinfunction "VOLUME_5") (pintype "passive"))
    )
    (net (code "48") (name "Net-(U5-BSLN)") (class "Default")
      (node (ref "C64") (pin "1") (pinfunction "1_1") (pintype "passive"))
      (node (ref "U5") (pin "15") (pinfunction "BSLN_15") (pintype "passive"))
    )
    (net (code "49") (name "Net-(U5-BSLP)") (class "Default")
      (node (ref "C65") (pin "1") (pinfunction "1_1") (pintype "passive"))
      (node (ref "U5") (pin "16") (pinfunction "BSLP_16") (pintype "passive"))
    )
    (net (code "50") (name "Net-(U5-BSRN)") (class "Default")
      (node (ref "C26") (pin "2") (pinfunction "2_2") (pintype "passive"))
      (node (ref "U5") (pin "36") (pinfunction "BSRN_36") (pintype "passive"))
    )
    (net (code "51") (name "Net-(U5-BSRP)") (class "Default")
      (node (ref "C27") (pin "1") (pinfunction "1_1") (pintype "passive"))
      (node (ref "U5") (pin "35") (pinfunction "BSRP_35") (pintype "passive"))
    )
    (net (code "52") (name "Net-(U5-COSC)") (class "Default")
      (node (ref "C50") (pin "1") (pinfunction "1_1") (pintype "passive"))
      (node (ref "U5") (pin "22") (pinfunction "COSC_22") (pintype "passive"))
    )
    (net (code "53") (name "Net-(U5-LINN)") (class "Default")
      (node (ref "C52") (pin "2") (pinfunction "2_2") (pintype "passive"))
      (node (ref "U5") (pin "10") (pinfunction "LINN_10") (pintype "passive"))
    )
    (net (code "54") (name "Net-(U5-LINP)") (class "Default")
      (node (ref "C49") (pin "2") (pinfunction "2_2") (pintype "passive"))
      (node (ref "U5") (pin "9") (pinfunction "LINP_9") (pintype "passive"))
    )
    (net (code "55") (name "Net-(U5-RINN)") (class "Default")
      (node (ref "C38") (pin "2") (pinfunction "2_2") (pintype "passive"))
      (node (ref "U5") (pin "1") (pinfunction "RINN_1") (pintype "passive"))
    )
    (net (code "56") (name "Net-(U5-RINP)") (class "Default")
      (node (ref "C40") (pin "2") (pinfunction "2_2") (pintype "passive"))
      (node (ref "U5") (pin "2") (pinfunction "RINP_2") (pintype "passive"))
    )
    (net (code "57") (name "Net-(U5-ROSC)") (class "Default")
      (node (ref "R16") (pin "2") (pinfunction "2_2") (pintype "passive"))
      (node (ref "U5") (pin "23") (pinfunction "ROSC_23") (pintype "passive"))
    )
    (net (code "58") (name "Net-(U5-V2P5)") (class "Default")
      (node (ref "C44") (pin "1") (pinfunction "1_1") (pintype "passive"))
      (node (ref "U5") (pin "27") (pinfunction "V2P5_27") (pintype "passive"))
    )
    (net (code "59") (name "Net-(U5-VCLAMPL)") (class "Default")
      (node (ref "C53") (pin "1") (pinfunction "1_1") (pintype "passive"))
      (node (ref "U5") (pin "21") (pinfunction "VCLAMPL_21") (pintype "passive"))
    )
    (net (code "60") (name "Net-(U5-VCLAMPR)") (class "Default")
      (node (ref "C39") (pin "1") (pinfunction "1_1") (pintype "passive"))
      (node (ref "U5") (pin "30") (pinfunction "VCLAMPR_30") (pintype "passive"))
    )
    (net (code "61") (name "Net-(U6-BST)") (class "Default")
      (node (ref "C70") (pin "2") (pinfunction "2_2") (pintype "passive"))
      (node (ref "U6") (pin "8") (pinfunction "BST_8") (pintype "passive"))
    )
    (net (code "62") (name "Net-(U6-COMP)") (class "Default")
      (node (ref "C75") (pin "2") (pinfunction "2_2") (pintype "passive"))
      (node (ref "U6") (pin "3") (pinfunction "COMP_3") (pintype "passive"))
    )
    (net (code "63") (name "Net-(U6-EN)") (class "Default")
      (node (ref "R25") (pin "2") (pintype "passive"))
      (node (ref "R29") (pin "1") (pintype "passive"))
      (node (ref "U6") (pin "2") (pinfunction "EN_2") (pintype "passive"))
    )
    (net (code "64") (name "Net-(U6-FB)") (class "Default")
      (node (ref "R26") (pin "1") (pintype "passive"))
      (node (ref "R28") (pin "1") (pintype "passive"))
      (node (ref "U6") (pin "4") (pinfunction "FB_4") (pintype "passive"))
    )
    (net (code "65") (name "Net-(U6-FREQ)") (class "Default")
      (node (ref "R30") (pin "1") (pintype "passive"))
      (node (ref "U6") (pin "6") (pinfunction "FREQ_6") (pintype "passive"))
    )
    (net (code "66") (name "VCC3.3") (class "Default")
      (node (ref "C57") (pin "1") (pinfunction "1_1") (pintype "passive"))
      (node (ref "C58") (pin "1") (pinfunction "1_1") (pintype "passive"))
      (node (ref "R24") (pin "1") (pinfunction "1_1") (pintype "passive"))
      (node (ref "U4") (pin "20") (pinfunction "PWR_IN_20") (pintype "passive"))
    )
    (net (code "67") (name "VCC12") (class "Default")
      (node (ref "C72") (pin "2") (pinfunction "2_2") (pintype "passive"))
      (node (ref "D11") (pin "1") (pinfunction "A_1") (pintype "passive"))
      (node (ref "D13") (pin "1") (pinfunction "A_1") (pintype "passive"))
      (node (ref "L1") (pin "2") (pinfunction "2_2") (pintype "passive"))
      (node (ref "R26") (pin "2") (pintype "passive"))
      (node (ref "R27") (pin "1") (pintype "passive"))
    )
    (net (code "68") (name "VCC24") (class "Default")
      (node (ref "C71") (pin "1") (pinfunction "1_1") (pintype "passive"))
      (node (ref "R25") (pin "1") (pintype "passive"))
      (node (ref "U6") (pin "7") (pinfunction "VIN_7") (pintype "passive"))
    )
    (net (code "69") (name "VDD12") (class "Default")
      (node (ref "C30") (pin "1") (pinfunction "1_1") (pintype "passive"))
      (node (ref "C45") (pin "1") (pinfunction "1_1") (pintype "passive"))
      (node (ref "C46") (pin "1") (pinfunction "1_1") (pintype "passive"))
      (node (ref "U4") (pin "1") (pinfunction "VDD12_1") (pintype "passive"))
      (node (ref "U4") (pin "23") (pinfunction "VDD12_O_23") (pintype "passive"))
    )
    (net (code "70") (name "VDD33") (class "Default")
      (node (ref "C28") (pin "1") (pinfunction "1_1") (pintype "passive"))
      (node (ref "C29") (pin "1") (pinfunction "1_1") (pintype "passive"))
      (node (ref "C36") (pin "1") (pinfunction "1_1") (pintype "passive"))
      (node (ref "C37") (pin "1") (pinfunction "1_1") (pintype "passive"))
      (node (ref "FB3") (pin "2") (pinfunction "2_2") (pintype "passive"))
      (node (ref "R14") (pin "2") (pinfunction "2_2") (pintype "passive"))
      (node (ref "R15") (pin "1") (pinfunction "1_1") (pintype "passive"))
      (node (ref "R19") (pin "2") (pinfunction "2_2") (pintype "passive"))
      (node (ref "R20") (pin "2") (pinfunction "2_2") (pintype "passive"))
      (node (ref "R22") (pin "1") (pinfunction "1_1") (pintype "passive"))
      (node (ref "R23") (pin "1") (pinfunction "1_1") (pintype "passive"))
      (node (ref "U4") (pin "22") (pinfunction "VDD33_O_22") (pintype "passive"))
      (node (ref "U4") (pin "36") (pinfunction "VDD33_36") (pintype "passive"))
      (node (ref "U4") (pin "46") (pinfunction "VDD33_46") (pintype "passive"))
    )
    (net (code "71") (name "unconnected-(U4-NC-Pad5)") (class "Default")
      (node (ref "U4") (pin "5") (pinfunction "NC_5") (pintype "passive"))
    )
    (net (code "72") (name "unconnected-(U4-NC-Pad6)") (class "Default")
      (node (ref "U4") (pin "6") (pinfunction "NC_6") (pintype "passive"))
    )
    (net (code "73") (name "unconnected-(U4-NC-Pad19)") (class "Default")
      (node (ref "U4") (pin "19") (pinfunction "NC_19") (pintype "passive"))
    )
    (net (code "74") (name "unconnected-(U4-NC-Pad30)") (class "Default")
      (node (ref "U4") (pin "30") (pinfunction "NC_30") (pintype "passive"))
    )
    (net (code "75") (name "unconnected-(U4-NC-Pad31)") (class "Default")
      (node (ref "U4") (pin "31") (pinfunction "NC_31") (pintype "passive"))
    )
    (net (code "76") (name "unconnected-(U4-NC-Pad32)") (class "Default")
      (node (ref "U4") (pin "32") (pinfunction "NC_32") (pintype "passive"))
    )
    (net (code "77") (name "unconnected-(U4-NC-Pad33)") (class "Default")
      (node (ref "U4") (pin "33") (pinfunction "NC_33") (pintype "passive"))
    )
    (net (code "78") (name "unconnected-(U4-NC-Pad34)") (class "Default")
      (node (ref "U4") (pin "34") (pinfunction "NC_34") (pintype "passive"))
    )
    (net (code "79") (name "unconnected-(U4-NC-Pad35)") (class "Default")
      (node (ref "U4") (pin "35") (pinfunction "NC_35") (pintype "passive"))
    )
    (net (code "80") (name "unconnected-(U4-NC-Pad38)") (class "Default")
      (node (ref "U4") (pin "38") (pinfunction "NC_38") (pintype "passive"))
    )
    (net (code "81") (name "unconnected-(U4-NC-Pad58)") (class "Default")
      (node (ref "U4") (pin "58") (pinfunction "NC_58") (pintype "passive"))
    )
    (net (code "82") (name "unconnected-(U4-NC-Pad61)") (class "Default")
      (node (ref "U4") (pin "61") (pinfunction "NC_61") (pintype "passive"))
    )
    (net (code "83") (name "unconnected-(U4-NC-Pad63)") (class "Default")
      (node (ref "U4") (pin "63") (pinfunction "NC_63") (pintype "passive"))
    )
  )
)
